# mcu_brd.net
KiCad netlist of a schematic drawn in EAGLE
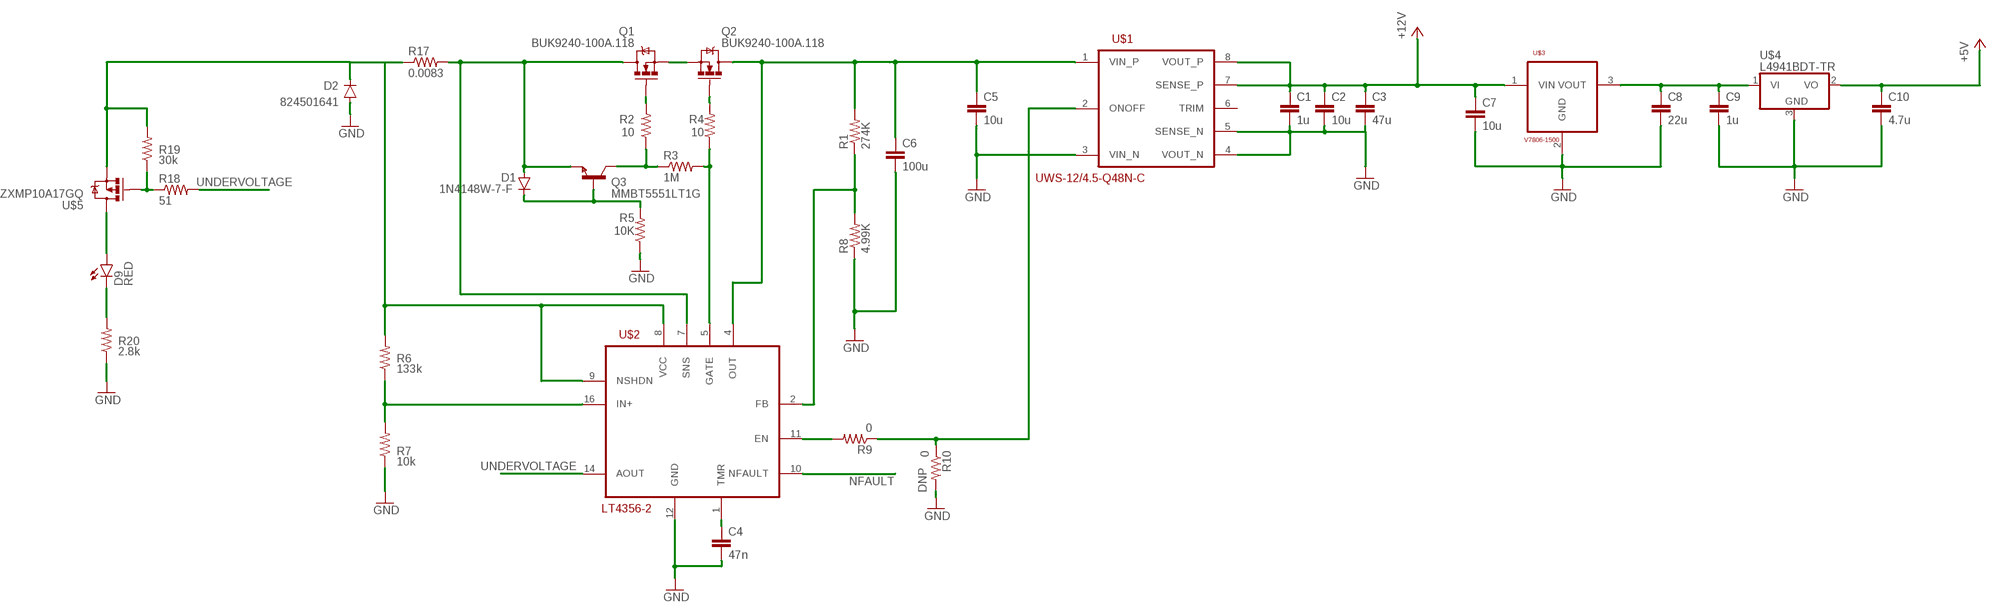
[diagram p0: schematic, sheet 1]
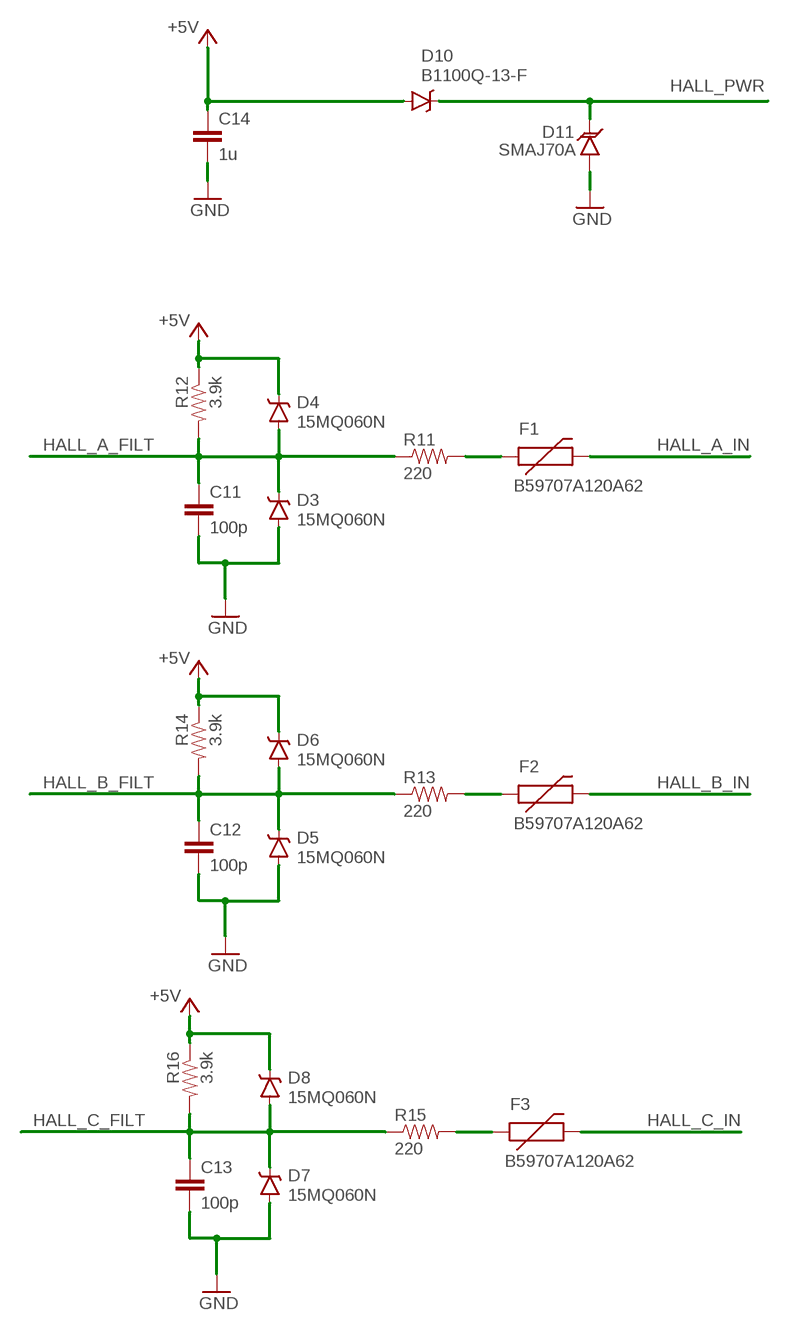
[diagram p1: schematic, sheet 2]

(export (version "E")
  (design (tool "Eeschema 10.0.6"))
  (components
    (comp (ref "C11")
      (value "100p")
      (footprint "eagle-import:1206")
      (libsource (lib "eagle-import") (part "CAP1206"))
    )
    (comp (ref "C12")
      (value "100p")
      (footprint "eagle-import:1206")
      (libsource (lib "eagle-import") (part "CAP1206"))
    )
    (comp (ref "C13")
      (value "100p")
      (footprint "eagle-import:1206")
      (libsource (lib "eagle-import") (part "CAP1206"))
    )
    (comp (ref "C14")
      (value "1u")
      (footprint "eagle-import:1206")
      (libsource (lib "eagle-import") (part "CAP1206"))
    )
    (comp (ref "D3")
      (value "15MQ060N")
      (footprint "eagle-import:SMA-DIODE")
      (libsource (lib "eagle-import") (part "DIODE-SCHOTTKY-B340A"))
    )
    (comp (ref "D4")
      (value "15MQ060N")
      (footprint "eagle-import:SMA-DIODE")
      (libsource (lib "eagle-import") (part "DIODE-SCHOTTKY-B340A"))
    )
    (comp (ref "D5")
      (value "15MQ060N")
      (footprint "eagle-import:SMA-DIODE")
      (libsource (lib "eagle-import") (part "DIODE-SCHOTTKY-B340A"))
    )
    (comp (ref "D6")
      (value "15MQ060N")
      (footprint "eagle-import:SMA-DIODE")
      (libsource (lib "eagle-import") (part "DIODE-SCHOTTKY-B340A"))
    )
    (comp (ref "D7")
      (value "15MQ060N")
      (footprint "eagle-import:SMA-DIODE")
      (libsource (lib "eagle-import") (part "DIODE-SCHOTTKY-B340A"))
    )
    (comp (ref "D8")
      (value "15MQ060N")
      (footprint "eagle-import:SMA-DIODE")
      (libsource (lib "eagle-import") (part "DIODE-SCHOTTKY-B340A"))
    )
    (comp (ref "D10")
      (value "B1100Q-13-F")
      (footprint "eagle-import:SMA-DIODE")
      (libsource (lib "eagle-import") (part "DIODE-SCHOTTKY-MBRA140"))
    )
    (comp (ref "D11")
      (value "SMAJ70A")
      (footprint "eagle-import:SMA-DIODE")
      (libsource (lib "eagle-import") (part "TVSSMA"))
    )
    (comp (ref "F1")
      (value "B59707A120A62")
      (footprint "eagle-import:PTC-1206")
      (libsource (lib "eagle-import") (part "PTCSMD"))
    )
    (comp (ref "F2")
      (value "B59707A120A62")
      (footprint "eagle-import:PTC-1206")
      (libsource (lib "eagle-import") (part "PTCSMD"))
    )
    (comp (ref "F3")
      (value "B59707A120A62")
      (footprint "eagle-import:PTC-1206")
      (libsource (lib "eagle-import") (part "PTCSMD"))
    )
    (comp (ref "R11")
      (value "220")
      (footprint "eagle-import:1206")
      (libsource (lib "eagle-import") (part "RESISTOR1206"))
    )
    (comp (ref "R12")
      (value "3.9k")
      (footprint "eagle-import:1206")
      (libsource (lib "eagle-import") (part "RESISTOR1206"))
    )
    (comp (ref "R13")
      (value "220")
      (footprint "eagle-import:1206")
      (libsource (lib "eagle-import") (part "RESISTOR1206"))
    )
    (comp (ref "R14")
      (value "3.9k")
      (footprint "eagle-import:1206")
      (libsource (lib "eagle-import") (part "RESISTOR1206"))
    )
    (comp (ref "R15")
      (value "220")
      (footprint "eagle-import:1206")
      (libsource (lib "eagle-import") (part "RESISTOR1206"))
    )
    (comp (ref "R16")
      (value "3.9k")
      (footprint "eagle-import:1206")
      (libsource (lib "eagle-import") (part "RESISTOR1206"))
    )
    (comp (ref "C1")
      (value "1u")
      (footprint "eagle-import:1206")
      (libsource (lib "eagle-import") (part "CAP1206"))
    )
    (comp (ref "C2")
      (value "10u")
      (footprint "eagle-import:1206")
      (libsource (lib "eagle-import") (part "CAP1206"))
    )
    (comp (ref "C3")
      (value "47u")
      (footprint "eagle-import:1206")
      (libsource (lib "eagle-import") (part "CAP1206"))
    )
    (comp (ref "C4")
      (value "47n")
      (footprint "eagle-import:0805")
      (libsource (lib "eagle-import") (part "CAP0805"))
    )
    (comp (ref "C5")
      (value "10u")
      (footprint "eagle-import:1210")
      (libsource (lib "eagle-import") (part "CAP1210"))
    )
    (comp (ref "C6")
      (value "100u")
      (footprint "eagle-import:1210")
      (libsource (lib "eagle-import") (part "CAP1210"))
    )
    (comp (ref "C7")
      (value "10u")
      (footprint "eagle-import:1206")
      (libsource (lib "eagle-import") (part "CAP1206"))
    )
    (comp (ref "C8")
      (value "22u")
      (footprint "eagle-import:1206")
      (libsource (lib "eagle-import") (part "CAP1206"))
    )
    (comp (ref "C9")
      (value "1u")
      (footprint "eagle-import:1206")
      (libsource (lib "eagle-import") (part "CAP1206"))
    )
    (comp (ref "C10")
      (value "4.7u")
      (footprint "eagle-import:1206")
      (libsource (lib "eagle-import") (part "CAP1206"))
    )
    (comp (ref "D1")
      (value "1N4148W-7-F")
      (footprint "eagle-import:SOD-123")
      (libsource (lib "eagle-import") (part "DIODESOD123"))
    )
    (comp (ref "D2")
      (value "824501641")
      (footprint "eagle-import:SMA-DIODE_ALT")
      (libsource (lib "eagle-import") (part "DIODESMA-ALT"))
    )
    (comp (ref "D9")
      (value "RED")
      (footprint "eagle-import:LED-1206")
      (libsource (lib "eagle-import") (part "LED-RED1206"))
    )
    (comp (ref "Q1")
      (value "BUK9240-100A.118")
      (footprint "eagle-import:DPAK")
      (libsource (lib "eagle-import") (part "MOSFET-NCHANNELFDD8780"))
    )
    (comp (ref "Q2")
      (value "BUK9240-100A.118")
      (footprint "eagle-import:DPAK")
      (libsource (lib "eagle-import") (part "MOSFET-NCHANNELFDD8780"))
    )
    (comp (ref "Q3")
      (value "MMBT5551LT1G")
      (footprint "eagle-import:SOT23-3")
      (libsource (lib "eagle-import") (part "TRANSISTOR_NPNMMBT2222A"))
    )
    (comp (ref "R1")
      (value "274K")
      (footprint "eagle-import:1206")
      (libsource (lib "eagle-import") (part "RESISTOR1206"))
    )
    (comp (ref "R2")
      (value "10")
      (footprint "eagle-import:1206")
      (libsource (lib "eagle-import") (part "RESISTOR1206"))
    )
    (comp (ref "R3")
      (value "1M")
      (footprint "eagle-import:1206")
      (libsource (lib "eagle-import") (part "RESISTOR1206"))
    )
    (comp (ref "R4")
      (value "10")
      (footprint "eagle-import:1206")
      (libsource (lib "eagle-import") (part "RESISTOR1206"))
    )
    (comp (ref "R5")
      (value "10K")
      (footprint "eagle-import:1206")
      (libsource (lib "eagle-import") (part "RESISTOR1206"))
    )
    (comp (ref "R6")
      (value "133k")
      (footprint "eagle-import:1206")
      (libsource (lib "eagle-import") (part "RESISTOR1206"))
    )
    (comp (ref "R7")
      (value "10k")
      (footprint "eagle-import:1206")
      (libsource (lib "eagle-import") (part "RESISTOR1206"))
    )
    (comp (ref "R8")
      (value "4.99K")
      (footprint "eagle-import:1206")
      (libsource (lib "eagle-import") (part "RESISTOR1206"))
    )
    (comp (ref "R9")
      (value "0")
      (footprint "eagle-import:0805")
      (libsource (lib "eagle-import") (part "RESISTOR0805-RES"))
    )
    (comp (ref "R10")
      (value "0")
      (footprint "eagle-import:0805")
      (libsource (lib "eagle-import") (part "RESISTOR0805-RES"))
    )
    (comp (ref "R17")
      (value "0.0083")
      (footprint "eagle-import:R2010")
      (libsource (lib "eagle-import") (part "RESISTOR2010"))
    )
    (comp (ref "R18")
      (value "51")
      (footprint "eagle-import:R2010")
      (libsource (lib "eagle-import") (part "RESISTOR2010"))
    )
    (comp (ref "R19")
      (value "30k")
      (footprint "eagle-import:1206")
      (libsource (lib "eagle-import") (part "RESISTOR1206"))
    )
    (comp (ref "R20")
      (value "2.8k")
      (footprint "eagle-import:1206")
      (libsource (lib "eagle-import") (part "RESISTOR1206"))
    )
    (comp (ref "U$1")
      (value "UWS-12/4.5-Q48N-C")
      (footprint "eagle-import:DOSA1_16")
      (libsource (lib "eagle-import") (part "UWS-12/4.5-Q48N-C"))
    )
    (comp (ref "U$2")
      (value "LT4356-2")
      (footprint "eagle-import:SOIC-16")
      (libsource (lib "eagle-import") (part "LT4356-1"))
    )
    (comp (ref "U$3")
      (value "V7806-1500")
      (footprint "eagle-import:V7806")
      (libsource (lib "eagle-import") (part "V7806-1500"))
    )
    (comp (ref "U$4")
      (value "L4941BDT-TR")
      (footprint "eagle-import:TO252")
      (libsource (lib "eagle-import") (part "78DT05"))
    )
    (comp (ref "U$5")
      (value "ZXMP10A17GQ")
      (footprint "eagle-import:SOT223")
      (libsource (lib "eagle-import") (part "ZXMP10A17GQ"))
    )
  )
  (nets
    (net (code "1") (name "+5V") (class "Default")
      (node (ref "C10") (pin "1") (pinfunction "1_1") (pintype "passive"))
      (node (ref "C14") (pin "1") (pinfunction "1_1") (pintype "passive"))
      (node (ref "D10") (pin "A") (pinfunction "A_A") (pintype "passive"))
      (node (ref "D4") (pin "C") (pinfunction "C_C") (pintype "passive"))
      (node (ref "D6") (pin "C") (pinfunction "C_C") (pintype "passive"))
      (node (ref "D8") (pin "C") (pinfunction "C_C") (pintype "passive"))
      (node (ref "R12") (pin "1") (pinfunction "1_1") (pintype "passive"))
      (node (ref "R14") (pin "1") (pinfunction "1_1") (pintype "passive"))
      (node (ref "R16") (pin "1") (pinfunction "1_1") (pintype "passive"))
      (node (ref "U$4") (pin "2") (pinfunction "VO_2") (pintype "passive"))
    )
    (net (code "2") (name "+12V") (class "Default")
      (node (ref "C1") (pin "1") (pinfunction "1_1") (pintype "passive"))
      (node (ref "C2") (pin "1") (pinfunction "1_1") (pintype "passive"))
      (node (ref "C3") (pin "1") (pinfunction "1_1") (pintype "passive"))
      (node (ref "C7") (pin "1") (pinfunction "1_1") (pintype "passive"))
      (node (ref "U$1") (pin "7") (pinfunction "SENSE_P_7") (pintype "bidirectional"))
      (node (ref "U$1") (pin "8") (pinfunction "VOUT_P_8") (pintype "power_in"))
      (node (ref "U$3") (pin "1") (pinfunction "VIN_1") (pintype "bidirectional"))
    )
    (net (code "3") (name "GND") (class "Default")
      (node (ref "C1") (pin "2") (pinfunction "2_2") (pintype "passive"))
      (node (ref "C10") (pin "2") (pinfunction "2_2") (pintype "passive"))
      (node (ref "C11") (pin "2") (pinfunction "2_2") (pintype "passive"))
      (node (ref "C12") (pin "2") (pinfunction "2_2") (pintype "passive"))
      (node (ref "C13") (pin "2") (pinfunction "2_2") (pintype "passive"))
      (node (ref "C14") (pin "2") (pinfunction "2_2") (pintype "passive"))
      (node (ref "C2") (pin "2") (pinfunction "2_2") (pintype "passive"))
      (node (ref "C3") (pin "2") (pinfunction "2_2") (pintype "passive"))
      (node (ref "C4") (pin "2") (pinfunction "2_2") (pintype "passive"))
      (node (ref "C5") (pin "2") (pinfunction "2_2") (pintype "passive"))
      (node (ref "C6") (pin "2") (pinfunction "2_2") (pintype "passive"))
      (node (ref "C7") (pin "2") (pinfunction "2_2") (pintype "passive"))
      (node (ref "C8") (pin "2") (pinfunction "2_2") (pintype "passive"))
      (node (ref "C9") (pin "2") (pinfunction "2_2") (pintype "passive"))
      (node (ref "D11") (pin "A") (pinfunction "A_A") (pintype "passive"))
      (node (ref "D2") (pin "A") (pinfunction "A_A") (pintype "passive"))
      (node (ref "D3") (pin "A") (pinfunction "A_A") (pintype "passive"))
      (node (ref "D5") (pin "A") (pinfunction "A_A") (pintype "passive"))
      (node (ref "D7") (pin "A") (pinfunction "A_A") (pintype "passive"))
      (node (ref "R10") (pin "2") (pinfunction "2_2") (pintype "passive"))
      (node (ref "R20") (pin "1") (pinfunction "1_1") (pintype "passive"))
      (node (ref "R5") (pin "1") (pinfunction "1_1") (pintype "passive"))
      (node (ref "R7") (pin "1") (pinfunction "1_1") (pintype "passive"))
      (node (ref "R8") (pin "1") (pinfunction "1_1") (pintype "passive"))
      (node (ref "U$1") (pin "3") (pinfunction "VIN_N_3") (pintype "power_in"))
      (node (ref "U$1") (pin "4") (pinfunction "VOUT_N_4") (pintype "power_in"))
      (node (ref "U$1") (pin "5") (pinfunction "SENSE_N_5") (pintype "bidirectional"))
      (node (ref "U$2") (pin "12") (pinfunction "GND_12") (pintype "bidirectional"))
      (node (ref "U$3") (pin "2") (pinfunction "GND_2") (pintype "bidirectional"))
      (node (ref "U$4") (pin "3") (pinfunction "GND_3") (pintype "passive"))
    )
    (net (code "4") (name "HALL_A_FILT") (class "Default")
      (node (ref "C11") (pin "1") (pinfunction "1_1") (pintype "passive"))
      (node (ref "D3") (pin "C") (pinfunction "C_C") (pintype "passive"))
      (node (ref "D4") (pin "A") (pinfunction "A_A") (pintype "passive"))
      (node (ref "R11") (pin "1") (pinfunction "1_1") (pintype "passive"))
      (node (ref "R12") (pin "2") (pinfunction "2_2") (pintype "passive"))
    )
    (net (code "5") (name "HALL_A_IN") (class "Default")
      (node (ref "F1") (pin "2") (pinfunction "2_2") (pintype "bidirectional"))
    )
    (net (code "6") (name "HALL_B_FILT") (class "Default")
      (node (ref "C12") (pin "1") (pinfunction "1_1") (pintype "passive"))
      (node (ref "D5") (pin "C") (pinfunction "C_C") (pintype "passive"))
      (node (ref "D6") (pin "A") (pinfunction "A_A") (pintype "passive"))
      (node (ref "R13") (pin "1") (pinfunction "1_1") (pintype "passive"))
      (node (ref "R14") (pin "2") (pinfunction "2_2") (pintype "passive"))
    )
    (net (code "7") (name "HALL_B_IN") (class "Default")
      (node (ref "F2") (pin "2") (pinfunction "2_2") (pintype "bidirectional"))
    )
    (net (code "8") (name "HALL_C_FILT") (class "Default")
      (node (ref "C13") (pin "1") (pinfunction "1_1") (pintype "passive"))
      (node (ref "D7") (pin "C") (pinfunction "C_C") (pintype "passive"))
      (node (ref "D8") (pin "A") (pinfunction "A_A") (pintype "passive"))
      (node (ref "R15") (pin "1") (pinfunction "1_1") (pintype "passive"))
      (node (ref "R16") (pin "2") (pinfunction "2_2") (pintype "passive"))
    )
    (net (code "9") (name "HALL_C_IN") (class "Default")
      (node (ref "F3") (pin "2") (pinfunction "2_2") (pintype "bidirectional"))
    )
    (net (code "10") (name "HALL_PWR") (class "Default")
      (node (ref "D10") (pin "C") (pinfunction "C_C") (pintype "passive"))
      (node (ref "D11") (pin "C") (pinfunction "C_C") (pintype "passive"))
    )
    (net (code "11") (name "NFAULT") (class "Default")
      (node (ref "U$2") (pin "10") (pinfunction "NFAULT_10") (pintype "bidirectional"))
    )
    (net (code "12") (name "Net-(D9-PadA)") (class "Default")
      (node (ref "D9") (pin "A") (pinfunction "A_A") (pintype "passive"))
      (node (ref "U$5") (pin "2") (pinfunction "D_2") (pintype "passive"))
      (node (ref "U$5") (pin "4") (pinfunction "D_4") (pintype "passive"))
    )
    (net (code "13") (name "Net-(D9-PadC)") (class "Default")
      (node (ref "D9") (pin "C") (pinfunction "C_C") (pintype "passive"))
      (node (ref "R20") (pin "2") (pinfunction "2_2") (pintype "passive"))
    )
    (net (code "14") (name "Net-(F1-Pad1)") (class "Default")
      (node (ref "F1") (pin "1") (pinfunction "1_1") (pintype "bidirectional"))
      (node (ref "R11") (pin "2") (pinfunction "2_2") (pintype "passive"))
    )
    (net (code "15") (name "Net-(F2-Pad1)") (class "Default")
      (node (ref "F2") (pin "1") (pinfunction "1_1") (pintype "bidirectional"))
      (node (ref "R13") (pin "2") (pinfunction "2_2") (pintype "passive"))
    )
    (net (code "16") (name "Net-(F3-Pad1)") (class "Default")
      (node (ref "F3") (pin "1") (pinfunction "1_1") (pintype "bidirectional"))
      (node (ref "R15") (pin "2") (pinfunction "2_2") (pintype "passive"))
    )
    (net (code "17") (name "Net-(Q1-D)") (class "Default")
      (node (ref "D1") (pin "A") (pinfunction "A_A") (pintype "passive"))
      (node (ref "Q1") (pin "4") (pinfunction "D_4") (pintype "passive"))
      (node (ref "Q3") (pin "2") (pinfunction "E_2") (pintype "passive"))
      (node (ref "R17") (pin "2") (pinfunction "2_2") (pintype "passive"))
      (node (ref "U$2") (pin "7") (pinfunction "SNS_7") (pintype "bidirectional"))
    )
    (net (code "18") (name "Net-(Q1-G)") (class "Default")
      (node (ref "Q1") (pin "1") (pinfunction "G_1") (pintype "passive"))
      (node (ref "R2") (pin "2") (pinfunction "2_2") (pintype "passive"))
    )
    (net (code "19") (name "Net-(Q1-S)") (class "Default")
      (node (ref "Q1") (pin "3") (pinfunction "S_3") (pintype "passive"))
      (node (ref "Q2") (pin "3") (pinfunction "S_3") (pintype "passive"))
    )
    (net (code "20") (name "Net-(Q2-D)") (class "Default")
      (node (ref "C5") (pin "1") (pinfunction "1_1") (pintype "passive"))
      (node (ref "C6") (pin "1") (pinfunction "1_1") (pintype "passive"))
      (node (ref "Q2") (pin "4") (pinfunction "D_4") (pintype "passive"))
      (node (ref "R1") (pin "2") (pinfunction "2_2") (pintype "passive"))
      (node (ref "U$1") (pin "1") (pinfunction "VIN_P_1") (pintype "power_in"))
      (node (ref "U$2") (pin "4") (pinfunction "OUT_4") (pintype "bidirectional"))
    )
    (net (code "21") (name "Net-(Q2-G)") (class "Default")
      (node (ref "Q2") (pin "1") (pinfunction "G_1") (pintype "passive"))
      (node (ref "R4") (pin "2") (pinfunction "2_2") (pintype "passive"))
    )
    (net (code "22") (name "Net-(Q3-B)") (class "Default")
      (node (ref "D1") (pin "C") (pinfunction "C_C") (pintype "passive"))
      (node (ref "Q3") (pin "1") (pinfunction "B_1") (pintype "passive"))
      (node (ref "R5") (pin "2") (pinfunction "2_2") (pintype "passive"))
    )
    (net (code "23") (name "Net-(Q3-C)") (class "Default")
      (node (ref "Q3") (pin "3") (pinfunction "C_3") (pintype "passive"))
      (node (ref "R2") (pin "1") (pinfunction "1_1") (pintype "passive"))
      (node (ref "R3") (pin "1") (pinfunction "1_1") (pintype "passive"))
    )
    (net (code "24") (name "Net-(U$1-ONOFF)") (class "Default")
      (node (ref "R10") (pin "1") (pinfunction "1_1") (pintype "passive"))
      (node (ref "R9") (pin "1") (pinfunction "1_1") (pintype "passive"))
      (node (ref "U$1") (pin "2") (pinfunction "ONOFF_2") (pintype "bidirectional"))
    )
    (net (code "25") (name "Net-(U$2-EN)") (class "Default")
      (node (ref "R9") (pin "2") (pinfunction "2_2") (pintype "passive"))
      (node (ref "U$2") (pin "11") (pinfunction "EN_11") (pintype "bidirectional"))
    )
    (net (code "26") (name "Net-(U$2-FB)") (class "Default")
      (node (ref "R1") (pin "1") (pinfunction "1_1") (pintype "passive"))
      (node (ref "R8") (pin "2") (pinfunction "2_2") (pintype "passive"))
      (node (ref "U$2") (pin "2") (pinfunction "FB_2") (pintype "bidirectional"))
    )
    (net (code "27") (name "Net-(U$2-GATE)") (class "Default")
      (node (ref "R3") (pin "2") (pinfunction "2_2") (pintype "passive"))
      (node (ref "R4") (pin "1") (pinfunction "1_1") (pintype "passive"))
      (node (ref "U$2") (pin "5") (pinfunction "GATE_5") (pintype "bidirectional"))
    )
    (net (code "28") (name "Net-(U$2-IN+)") (class "Default")
      (node (ref "R6") (pin "1") (pinfunction "1_1") (pintype "passive"))
      (node (ref "R7") (pin "2") (pinfunction "2_2") (pintype "passive"))
      (node (ref "U$2") (pin "16") (pinfunction "IN+_16") (pintype "bidirectional"))
    )
    (net (code "29") (name "Net-(U$2-NSHDN)") (class "Default")
      (node (ref "D2") (pin "C") (pinfunction "C_C") (pintype "passive"))
      (node (ref "R17") (pin "1") (pinfunction "1_1") (pintype "passive"))
      (node (ref "R19") (pin "2") (pinfunction "2_2") (pintype "passive"))
      (node (ref "R6") (pin "2") (pinfunction "2_2") (pintype "passive"))
      (node (ref "U$2") (pin "8") (pinfunction "VCC_8") (pintype "bidirectional"))
      (node (ref "U$2") (pin "9") (pinfunction "NSHDN_9") (pintype "bidirectional"))
      (node (ref "U$5") (pin "3") (pinfunction "S_3") (pintype "passive"))
    )
    (net (code "30") (name "Net-(U$2-TMR)") (class "Default")
      (node (ref "C4") (pin "1") (pinfunction "1_1") (pintype "passive"))
      (node (ref "U$2") (pin "1") (pinfunction "TMR_1") (pintype "bidirectional"))
    )
    (net (code "31") (name "Net-(U$3-VOUT)") (class "Default")
      (node (ref "C8") (pin "1") (pinfunction "1_1") (pintype "passive"))
      (node (ref "C9") (pin "1") (pinfunction "1_1") (pintype "passive"))
      (node (ref "U$3") (pin "3") (pinfunction "VOUT_3") (pintype "bidirectional"))
      (node (ref "U$4") (pin "1") (pinfunction "VI_1") (pintype "input"))
    )
    (net (code "32") (name "Net-(U$5-G)") (class "Default")
      (node (ref "R18") (pin "1") (pinfunction "1_1") (pintype "passive"))
      (node (ref "R19") (pin "1") (pinfunction "1_1") (pintype "passive"))
      (node (ref "U$5") (pin "1") (pinfunction "G_1") (pintype "passive"))
    )
    (net (code "33") (name "UNDERVOLTAGE") (class "Default")
      (node (ref "R18") (pin "2") (pinfunction "2_2") (pintype "passive"))
      (node (ref "U$2") (pin "14") (pinfunction "AOUT_14") (pintype "bidirectional"))
    )
    (net (code "34") (name "unconnected-(U$1-TRIM-Pad6)") (class "Default")
      (node (ref "U$1") (pin "6") (pinfunction "TRIM_6") (pintype "bidirectional"))
    )
  )
)
